# sc.net
KiCad netlist of a schematic drawn in EAGLE
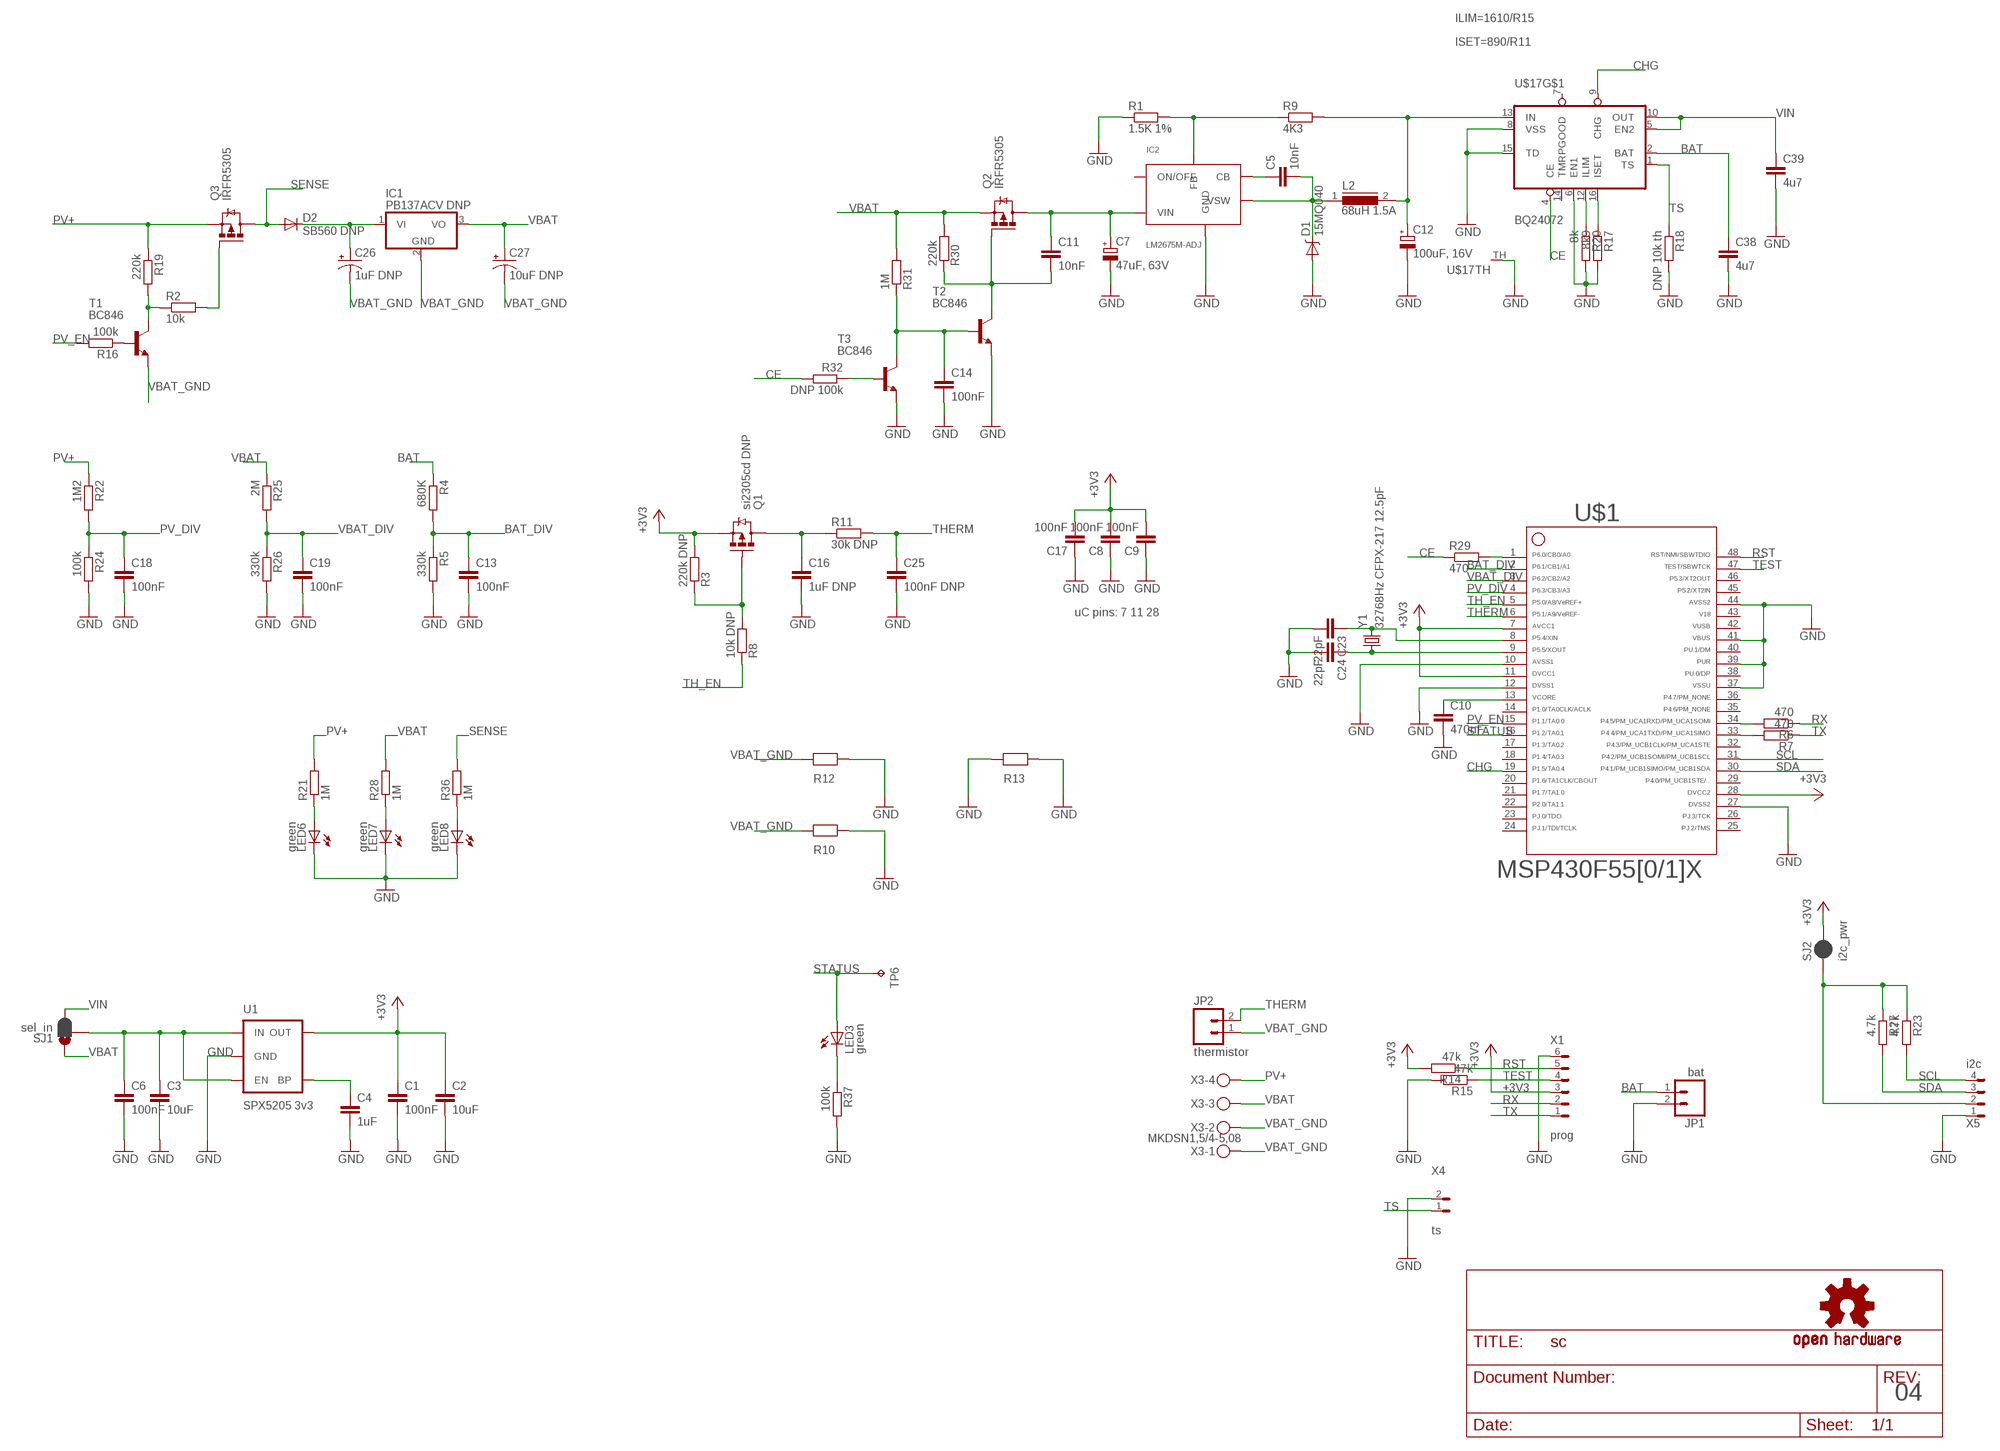
[diagram p0: schematic, sheet 1]

(export (version "E")
  (design (tool "Eeschema 10.0.6"))
  (components
    (comp (ref "C1")
      (value "100nF")
      (footprint "eagle-import:C0805")
      (libsource (lib "eagle-import") (part "C-EUC0805"))
    )
    (comp (ref "C2")
      (value "10uF")
      (footprint "eagle-import:C1206")
      (libsource (lib "eagle-import") (part "C-EUC1206"))
    )
    (comp (ref "C3")
      (value "10uF")
      (footprint "eagle-import:C1206")
      (libsource (lib "eagle-import") (part "C-EUC1206"))
    )
    (comp (ref "C4")
      (value "1uF")
      (footprint "eagle-import:C0805")
      (libsource (lib "eagle-import") (part "C-EUC0805"))
    )
    (comp (ref "C5")
      (value "10nF")
      (footprint "eagle-import:C0805")
      (libsource (lib "eagle-import") (part "C-EUC0805"))
    )
    (comp (ref "C6")
      (value "100nF")
      (footprint "eagle-import:C0805")
      (libsource (lib "eagle-import") (part "C-EUC0805"))
    )
    (comp (ref "C7")
      (value "47uF, 63V")
      (footprint "eagle-import:PANASONIC_F")
      (libsource (lib "eagle-import") (part "CPOL-EUF"))
    )
    (comp (ref "C8")
      (value "100nF")
      (footprint "eagle-import:C0805")
      (libsource (lib "eagle-import") (part "C-EUC0805"))
    )
    (comp (ref "C9")
      (value "100nF")
      (footprint "eagle-import:C0805")
      (libsource (lib "eagle-import") (part "C-EUC0805"))
    )
    (comp (ref "C10")
      (value "470nF")
      (footprint "eagle-import:C0805")
      (libsource (lib "eagle-import") (part "C-EUC0805"))
    )
    (comp (ref "C11")
      (value "10nF")
      (footprint "eagle-import:C0805")
      (libsource (lib "eagle-import") (part "C-EUC0805"))
    )
    (comp (ref "C12")
      (value "100uF, 16V")
      (footprint "eagle-import:PANASONIC_D")
      (libsource (lib "eagle-import") (part "CPOL-EUD"))
    )
    (comp (ref "C13")
      (value "100nF")
      (footprint "eagle-import:C0805")
      (libsource (lib "eagle-import") (part "C-EUC0805"))
    )
    (comp (ref "C14")
      (value "100nF")
      (footprint "eagle-import:C0805")
      (libsource (lib "eagle-import") (part "C-EUC0805"))
    )
    (comp (ref "C16")
      (value "1uF DNP")
      (footprint "eagle-import:C0805")
      (libsource (lib "eagle-import") (part "C-EUC0805"))
    )
    (comp (ref "C17")
      (value "100nF")
      (footprint "eagle-import:C0805")
      (libsource (lib "eagle-import") (part "C-EUC0805"))
    )
    (comp (ref "C18")
      (value "100nF")
      (footprint "eagle-import:C0805")
      (libsource (lib "eagle-import") (part "C-EUC0805"))
    )
    (comp (ref "C19")
      (value "100nF")
      (footprint "eagle-import:C0805")
      (libsource (lib "eagle-import") (part "C-EUC0805"))
    )
    (comp (ref "C23")
      (value "22pF")
      (footprint "eagle-import:C0805")
      (libsource (lib "eagle-import") (part "C-EUC0805"))
    )
    (comp (ref "C24")
      (value "22pF")
      (footprint "eagle-import:C0805")
      (libsource (lib "eagle-import") (part "C-EUC0805"))
    )
    (comp (ref "C25")
      (value "100nF DNP")
      (footprint "eagle-import:C0805")
      (libsource (lib "eagle-import") (part "C-EUC0805"))
    )
    (comp (ref "C26")
      (value "1uF DNP")
      (footprint "eagle-import:PANASONIC_D")
      (libsource (lib "eagle-import") (part "CAP_POLD"))
    )
    (comp (ref "C27")
      (value "10uF DNP")
      (footprint "eagle-import:PANASONIC_D")
      (libsource (lib "eagle-import") (part "CAP_POLD"))
    )
    (comp (ref "C38")
      (value "4u7")
      (footprint "eagle-import:C1206")
      (libsource (lib "eagle-import") (part "C-EUC1206"))
    )
    (comp (ref "C39")
      (value "4u7")
      (footprint "eagle-import:C1206")
      (libsource (lib "eagle-import") (part "C-EUC1206"))
    )
    (comp (ref "D1")
      (value "15MQ040")
      (footprint "eagle-import:SMA-DIODE")
      (libsource (lib "eagle-import") (part "DIODE-SCHOTTKY-MBRA140"))
    )
    (comp (ref "D2")
      (value "SB560 DNP")
      (footprint "eagle-import:C1702-05")
      (libsource (lib "eagle-import") (part "DIODE-C1702-05"))
    )
    (comp (ref "IC1")
      (value "PB137ACV DNP")
      (footprint "eagle-import:TO220V")
      (libsource (lib "eagle-import") (part "78TV12"))
    )
    (comp (ref "IC2")
      (value "LM2675M-ADJ")
      (footprint "eagle-import:SO-08")
      (libsource (lib "eagle-import") (part "LM2674"))
    )
    (comp (ref "JP1")
      (value "bat")
      (footprint "eagle-import:1X02")
      (libsource (lib "eagle-import") (part "M02PTH"))
    )
    (comp (ref "JP2")
      (value "thermistor")
      (footprint "eagle-import:1X02")
      (libsource (lib "eagle-import") (part "M02PTH"))
    )
    (comp (ref "L2")
      (value "68uH 1.5A")
      (footprint "eagle-import:DR125")
      (libsource (lib "eagle-import") (part "DR125"))
    )
    (comp (ref "LED3")
      (value "green")
      (footprint "eagle-import:CHIPLED_0805")
      (libsource (lib "eagle-import") (part "LEDCHIPLED_0805"))
    )
    (comp (ref "LED6")
      (value "green")
      (footprint "eagle-import:CHIP-LED0805")
      (libsource (lib "eagle-import") (part "LEDCHIP-LED0805"))
    )
    (comp (ref "LED7")
      (value "green")
      (footprint "eagle-import:CHIP-LED0805")
      (libsource (lib "eagle-import") (part "LEDCHIP-LED0805"))
    )
    (comp (ref "LED8")
      (value "green")
      (footprint "eagle-import:CHIP-LED0805")
      (libsource (lib "eagle-import") (part "LEDCHIP-LED0805"))
    )
    (comp (ref "Q1")
      (value "si2305cd DNP")
      (footprint "eagle-import:SOT23-3_POWER@1")
      (libsource (lib "eagle-import") (part "MOSFET-PCHANNELSMD_POWER"))
    )
    (comp (ref "Q2")
      (value "IRFR5305")
      (footprint "eagle-import:D-PAK_TO252AA")
      (libsource (lib "eagle-import") (part "IRF?5305R"))
    )
    (comp (ref "Q3")
      (value "IRFR5305")
      (footprint "eagle-import:D-PAK_TO252AA")
      (libsource (lib "eagle-import") (part "IRF?5305R"))
    )
    (comp (ref "R1")
      (value "1.5K 1%")
      (footprint "eagle-import:R0805W")
      (libsource (lib "eagle-import") (part "R-EU_R0805W"))
    )
    (comp (ref "R2")
      (value "10k")
      (footprint "eagle-import:R0805W")
      (libsource (lib "eagle-import") (part "R-EU_R0805W"))
    )
    (comp (ref "R3")
      (value "220k DNP")
      (footprint "eagle-import:R0805W")
      (libsource (lib "eagle-import") (part "R-EU_R0805W"))
    )
    (comp (ref "R4")
      (value "680K")
      (footprint "eagle-import:R0805W")
      (libsource (lib "eagle-import") (part "R-EU_R0805W"))
    )
    (comp (ref "R5")
      (value "330k")
      (footprint "eagle-import:R0805W")
      (libsource (lib "eagle-import") (part "R-EU_R0805W"))
    )
    (comp (ref "R6")
      (value "470")
      (footprint "eagle-import:R0805W")
      (libsource (lib "eagle-import") (part "R-EU_R0805W"))
    )
    (comp (ref "R7")
      (value "470")
      (footprint "eagle-import:R0805W")
      (libsource (lib "eagle-import") (part "R-EU_R0805W"))
    )
    (comp (ref "R8")
      (value "10k DNP")
      (footprint "eagle-import:R0805W")
      (libsource (lib "eagle-import") (part "R-EU_R0805W"))
    )
    (comp (ref "R9")
      (value "4K3")
      (footprint "eagle-import:R0805W")
      (libsource (lib "eagle-import") (part "R-EU_R0805W"))
    )
    (comp (ref "R10")
      (value "0R_0805")
      (footprint "eagle-import:R0805W")
      (libsource (lib "eagle-import") (part "0R_0805"))
    )
    (comp (ref "R11")
      (value "30k DNP")
      (footprint "eagle-import:R0805W")
      (libsource (lib "eagle-import") (part "R-EU_R0805W"))
    )
    (comp (ref "R12")
      (value "0R_0805")
      (footprint "eagle-import:R0805W")
      (libsource (lib "eagle-import") (part "0R_0805"))
    )
    (comp (ref "R13")
      (value "0R_0805")
      (footprint "eagle-import:R0805W")
      (libsource (lib "eagle-import") (part "0R_0805"))
    )
    (comp (ref "R14")
      (value "47k")
      (footprint "eagle-import:R0805W")
      (libsource (lib "eagle-import") (part "R-EU_R0805W"))
    )
    (comp (ref "R15")
      (value "47k")
      (footprint "eagle-import:R0805W")
      (libsource (lib "eagle-import") (part "R-EU_R0805W"))
    )
    (comp (ref "R16")
      (value "100k")
      (footprint "eagle-import:R0805W")
      (libsource (lib "eagle-import") (part "R-EU_R0805W"))
    )
    (comp (ref "R17")
      (value "8k9")
      (footprint "eagle-import:R0805W")
      (libsource (lib "eagle-import") (part "R-EU_R0805W"))
    )
    (comp (ref "R18")
      (value "DNP 10k th")
      (footprint "eagle-import:R0805W")
      (libsource (lib "eagle-import") (part "R-EU_R0805W"))
    )
    (comp (ref "R19")
      (value "220k")
      (footprint "eagle-import:R0805W")
      (libsource (lib "eagle-import") (part "R-EU_R0805W"))
    )
    (comp (ref "R20")
      (value "8k")
      (footprint "eagle-import:R0805W")
      (libsource (lib "eagle-import") (part "R-EU_R0805W"))
    )
    (comp (ref "R21")
      (value "1M")
      (footprint "eagle-import:R0805W")
      (libsource (lib "eagle-import") (part "R-EU_R0805W"))
    )
    (comp (ref "R22")
      (value "1M2")
      (footprint "eagle-import:R0805W")
      (libsource (lib "eagle-import") (part "R-EU_R0805W"))
    )
    (comp (ref "R23")
      (value "4.7k")
      (footprint "eagle-import:R0805W")
      (libsource (lib "eagle-import") (part "R-EU_R0805W"))
    )
    (comp (ref "R24")
      (value "100k")
      (footprint "eagle-import:R0805W")
      (libsource (lib "eagle-import") (part "R-EU_R0805W"))
    )
    (comp (ref "R25")
      (value "2M")
      (footprint "eagle-import:R0805W")
      (libsource (lib "eagle-import") (part "R-EU_R0805W"))
    )
    (comp (ref "R26")
      (value "330k")
      (footprint "eagle-import:R0805W")
      (libsource (lib "eagle-import") (part "R-EU_R0805W"))
    )
    (comp (ref "R27")
      (value "4.7k")
      (footprint "eagle-import:R0805W")
      (libsource (lib "eagle-import") (part "R-EU_R0805W"))
    )
    (comp (ref "R28")
      (value "1M")
      (footprint "eagle-import:R0805W")
      (libsource (lib "eagle-import") (part "R-EU_R0805W"))
    )
    (comp (ref "R29")
      (value "470")
      (footprint "eagle-import:R0805W")
      (libsource (lib "eagle-import") (part "R-EU_R0805W"))
    )
    (comp (ref "R30")
      (value "220k")
      (footprint "eagle-import:R0805W")
      (libsource (lib "eagle-import") (part "R-EU_R0805W"))
    )
    (comp (ref "R31")
      (value "1M")
      (footprint "eagle-import:R0805W")
      (libsource (lib "eagle-import") (part "R-EU_R0805W"))
    )
    (comp (ref "R32")
      (value "DNP 100k")
      (footprint "eagle-import:R0805W")
      (libsource (lib "eagle-import") (part "R-EU_R0805W"))
    )
    (comp (ref "R36")
      (value "1M")
      (footprint "eagle-import:R0805W")
      (libsource (lib "eagle-import") (part "R-EU_R0805W"))
    )
    (comp (ref "R37")
      (value "100k")
      (footprint "eagle-import:R0805W")
      (libsource (lib "eagle-import") (part "R-EU_R0805W"))
    )
    (comp (ref "SJ1")
      (value "sel_in")
      (footprint "eagle-import:PAD-JUMPER-3-2OF3_NC_BY_PASTE_YES_SILK_FULL_BOX")
      (libsource (lib "eagle-import") (part "JUMPER-PAD-3-2OF3_NC_BY_PASTE"))
    )
    (comp (ref "SJ2")
      (value "i2c_pwr")
      (footprint "eagle-import:PAD-JUMPER-2-NC_BY_PASTE_YES_SILK")
      (libsource (lib "eagle-import") (part "JUMPER-PAD-2-NC_BY_PASTE"))
    )
    (comp (ref "T1")
      (value "BC846")
      (footprint "eagle-import:SOT23")
      (libsource (lib "eagle-import") (part "BC846"))
    )
    (comp (ref "T2")
      (value "BC846")
      (footprint "eagle-import:SOT23")
      (libsource (lib "eagle-import") (part "BC846"))
    )
    (comp (ref "T3")
      (value "BC846")
      (footprint "eagle-import:SOT23")
      (libsource (lib "eagle-import") (part "BC846"))
    )
    (comp (ref "TP6")
      (value "TPTP12R")
      (footprint "eagle-import:TP12R")
      (libsource (lib "eagle-import") (part "TPTP12R"))
    )
    (comp (ref "U$1")
      (value "F55[0/1]X---PT48")
      (footprint "eagle-import:PT48")
      (libsource (lib "eagle-import") (part "F55[0/1]X---PT48"))
    )
    (comp (ref "U$7")
      (value "OSHW-LOGOM")
      (footprint "eagle-import:OSHW-LOGO-M")
      (libsource (lib "eagle-import") (part "OSHW-LOGOM"))
    )
    (comp (ref "U$17")
      (value "BQ24072")
      (footprint "eagle-import:S-PVQFN-N16")
      (libsource (lib "eagle-import") (part "BQ24072"))
    )
    (comp (ref "U1")
      (value "SPX5205 3v3")
      (footprint "eagle-import:SOT23-5")
      (libsource (lib "eagle-import") (part "V_REG_LDOSMD"))
    )
    (comp (ref "X1")
      (value "prog")
      (footprint "eagle-import:0530480610")
      (libsource (lib "eagle-import") (part "MOLEX_6HORIZONTAL"))
    )
    (comp (ref "X3")
      (value "MKDSN1,5/4-5,08")
      (footprint "eagle-import:MKDSN1,5_4-5,08")
      (fields (field (name "MPN") "SMKDSN1,5/4-5,08"))
      (libsource (lib "eagle-import") (part "MKDSN1,5/4-5,08"))
    )
    (comp (ref "X4")
      (value "ts")
      (footprint "eagle-import:0530480210")
      (libsource (lib "eagle-import") (part "MOLEX_2HORIZONTAL"))
    )
    (comp (ref "X5")
      (value "i2c")
      (footprint "eagle-import:0530480401")
      (libsource (lib "eagle-import") (part "MOLEX_4HORIZONTAL"))
    )
    (comp (ref "Y1")
      (value "32768Hz CFPX-217 12.5pF")
      (footprint "eagle-import:CRYSTAL-SMD-3.2X1.5")
      (libsource (lib "eagle-import") (part "CRYSTAL3.2X1.5"))
    )
  )
  (nets
    (net (code "1") (name "+3V3") (class "Default")
      (node (ref "C1") (pin "1") (pinfunction "1_1") (pintype "passive"))
      (node (ref "C17") (pin "2") (pinfunction "2_2") (pintype "passive"))
      (node (ref "C2") (pin "1") (pinfunction "1_1") (pintype "passive"))
      (node (ref "C8") (pin "2") (pinfunction "2_2") (pintype "passive"))
      (node (ref "C9") (pin "2") (pinfunction "2_2") (pintype "passive"))
      (node (ref "Q1") (pin "2") (pinfunction "S_2") (pintype "passive"))
      (node (ref "R14") (pin "2") (pinfunction "2_2") (pintype "passive"))
      (node (ref "R3") (pin "2") (pinfunction "2_2") (pintype "passive"))
      (node (ref "SJ2") (pin "2") (pinfunction "2_2") (pintype "passive"))
      (node (ref "U$1") (pin "11") (pinfunction "11_11") (pintype "power_in"))
      (node (ref "U$1") (pin "28") (pinfunction "28_28") (pintype "power_in"))
      (node (ref "U$1") (pin "7") (pinfunction "7_7") (pintype "power_in"))
      (node (ref "U1") (pin "5") (pinfunction "OUT_5") (pintype "passive"))
      (node (ref "X1") (pin "3") (pinfunction "4_3") (pintype "passive"))
    )
    (net (code "2") (name "/42") (class "Default")
      (node (ref "U$1") (pin "42") (pinfunction "42_42") (pintype "power_in"))
    )
    (net (code "3") (name "/43") (class "Default")
      (node (ref "U$1") (pin "43") (pinfunction "43_43") (pintype "power_in"))
    )
    (net (code "4") (name "/46") (class "Default")
      (node (ref "U$1") (pin "46") (pinfunction "46_46") (pintype "power_in"))
    )
    (net (code "5") (name "/BAT") (class "Default")
      (node (ref "C38") (pin "1") (pinfunction "1_1") (pintype "passive"))
      (node (ref "JP1") (pin "1") (pinfunction "1_1") (pintype "passive"))
      (node (ref "R4") (pin "1") (pinfunction "1_1") (pintype "passive"))
      (node (ref "U$17") (pin "2") (pinfunction "BAT_2") (pintype "input"))
    )
    (net (code "6") (name "/BAT_DIV") (class "Default")
      (node (ref "C13") (pin "1") (pinfunction "1_1") (pintype "passive"))
      (node (ref "R4") (pin "2") (pinfunction "2_2") (pintype "passive"))
      (node (ref "R5") (pin "1") (pinfunction "1_1") (pintype "passive"))
      (node (ref "U$1") (pin "2") (pinfunction "2_2") (pintype "bidirectional"))
    )
    (net (code "7") (name "/CE") (class "Default")
      (node (ref "R29") (pin "1") (pinfunction "1_1") (pintype "passive"))
      (node (ref "R32") (pin "2") (pinfunction "2_2") (pintype "passive"))
      (node (ref "U$17") (pin "4") (pinfunction "CE_4") (pintype "bidirectional"))
    )
    (net (code "8") (name "/CHG") (class "Default")
      (node (ref "U$1") (pin "19") (pinfunction "19_19") (pintype "bidirectional"))
      (node (ref "U$17") (pin "9") (pinfunction "CHG_9") (pintype "bidirectional"))
    )
    (net (code "9") (name "/PV+") (class "Default")
      (node (ref "Q3") (pin "3") (pinfunction "S_3") (pintype "passive"))
      (node (ref "R19") (pin "1") (pinfunction "1_1") (pintype "passive"))
      (node (ref "R21") (pin "2") (pinfunction "2_2") (pintype "passive"))
      (node (ref "R22") (pin "1") (pinfunction "1_1") (pintype "passive"))
      (node (ref "X3") (pin "4") (pinfunction "KL_4") (pintype "passive"))
    )
    (net (code "10") (name "/PV_DIV") (class "Default")
      (node (ref "C18") (pin "1") (pinfunction "1_1") (pintype "passive"))
      (node (ref "R22") (pin "2") (pinfunction "2_2") (pintype "passive"))
      (node (ref "R24") (pin "1") (pinfunction "1_1") (pintype "passive"))
      (node (ref "U$1") (pin "4") (pinfunction "4_4") (pintype "bidirectional"))
    )
    (net (code "11") (name "/PV_EN") (class "Default")
      (node (ref "R16") (pin "2") (pinfunction "2_2") (pintype "passive"))
      (node (ref "U$1") (pin "15") (pinfunction "15_15") (pintype "bidirectional"))
    )
    (net (code "12") (name "/RST") (class "Default")
      (node (ref "R14") (pin "1") (pinfunction "1_1") (pintype "passive"))
      (node (ref "U$1") (pin "48") (pinfunction "48_48") (pintype "bidirectional"))
      (node (ref "X1") (pin "5") (pinfunction "2_5") (pintype "passive"))
    )
    (net (code "13") (name "/RX") (class "Default")
      (node (ref "R6") (pin "1") (pinfunction "1_1") (pintype "passive"))
      (node (ref "X1") (pin "2") (pinfunction "5_2") (pintype "passive"))
    )
    (net (code "14") (name "/SCL") (class "Default")
      (node (ref "R23") (pin "2") (pinfunction "2_2") (pintype "passive"))
      (node (ref "U$1") (pin "31") (pinfunction "31_31") (pintype "bidirectional"))
      (node (ref "X5") (pin "4") (pinfunction "1_4") (pintype "passive"))
    )
    (net (code "15") (name "/SDA") (class "Default")
      (node (ref "R27") (pin "2") (pinfunction "2_2") (pintype "passive"))
      (node (ref "U$1") (pin "30") (pinfunction "30_30") (pintype "bidirectional"))
      (node (ref "X5") (pin "3") (pinfunction "2_3") (pintype "passive"))
    )
    (net (code "16") (name "/SENSE") (class "Default")
      (node (ref "D2") (pin "A") (pinfunction "A_A") (pintype "passive"))
      (node (ref "Q3") (pin "4") (pinfunction "D_4") (pintype "passive"))
      (node (ref "R36") (pin "2") (pinfunction "2_2") (pintype "passive"))
    )
    (net (code "17") (name "/STATUS") (class "Default")
      (node (ref "LED3") (pin "A") (pinfunction "A_A") (pintype "passive"))
      (node (ref "TP6") (pin "TP") (pinfunction "TP_TP") (pintype "input"))
      (node (ref "U$1") (pin "16") (pinfunction "16_16") (pintype "bidirectional"))
    )
    (net (code "18") (name "/TEST") (class "Default")
      (node (ref "R15") (pin "1") (pinfunction "1_1") (pintype "passive"))
      (node (ref "U$1") (pin "47") (pinfunction "47_47") (pintype "input"))
      (node (ref "X1") (pin "4") (pinfunction "3_4") (pintype "passive"))
    )
    (net (code "19") (name "/THERM") (class "Default")
      (node (ref "C25") (pin "1") (pinfunction "1_1") (pintype "passive"))
      (node (ref "JP2") (pin "2") (pinfunction "2_2") (pintype "passive"))
      (node (ref "R11") (pin "2") (pinfunction "2_2") (pintype "passive"))
      (node (ref "U$1") (pin "6") (pinfunction "6_6") (pintype "bidirectional"))
    )
    (net (code "20") (name "/TH_EN") (class "Default")
      (node (ref "R8") (pin "1") (pinfunction "1_1") (pintype "passive"))
      (node (ref "U$1") (pin "5") (pinfunction "5_5") (pintype "bidirectional"))
    )
    (net (code "21") (name "/TS") (class "Default")
      (node (ref "R18") (pin "1") (pinfunction "1_1") (pintype "passive"))
      (node (ref "U$17") (pin "1") (pinfunction "TS_1") (pintype "input"))
      (node (ref "X4") (pin "1") (pinfunction "2_1") (pintype "passive"))
    )
    (net (code "22") (name "/TX") (class "Default")
      (node (ref "R7") (pin "1") (pinfunction "1_1") (pintype "passive"))
      (node (ref "X1") (pin "1") (pinfunction "6_1") (pintype "passive"))
    )
    (net (code "23") (name "/VBAT") (class "Default")
      (node (ref "C27") (pin "+") (pinfunction "+_+") (pintype "passive"))
      (node (ref "IC1") (pin "3") (pinfunction "VO_3") (pintype "passive"))
      (node (ref "Q2") (pin "3") (pinfunction "S_3") (pintype "passive"))
      (node (ref "R25") (pin "1") (pinfunction "1_1") (pintype "passive"))
      (node (ref "R28") (pin "2") (pinfunction "2_2") (pintype "passive"))
      (node (ref "R30") (pin "2") (pinfunction "2_2") (pintype "passive"))
      (node (ref "R31") (pin "2") (pinfunction "2_2") (pintype "passive"))
      (node (ref "SJ1") (pin "1") (pinfunction "1_1") (pintype "passive"))
      (node (ref "X3") (pin "3") (pinfunction "KL_3") (pintype "passive"))
    )
    (net (code "24") (name "/VBAT_DIV") (class "Default")
      (node (ref "C19") (pin "1") (pinfunction "1_1") (pintype "passive"))
      (node (ref "R25") (pin "2") (pinfunction "2_2") (pintype "passive"))
      (node (ref "R26") (pin "1") (pinfunction "1_1") (pintype "passive"))
      (node (ref "U$1") (pin "3") (pinfunction "3_3") (pintype "bidirectional"))
    )
    (net (code "25") (name "/VBAT_GND") (class "Default")
      (node (ref "C26") (pin "-") (pinfunction "-_-") (pintype "passive"))
      (node (ref "C27") (pin "-") (pinfunction "-_-") (pintype "passive"))
      (node (ref "IC1") (pin "2") (pinfunction "GND_2") (pintype "passive"))
      (node (ref "JP2") (pin "1") (pinfunction "1_1") (pintype "passive"))
      (node (ref "R10") (pin "1") (pinfunction "P$1_1") (pintype "bidirectional"))
      (node (ref "R12") (pin "1") (pinfunction "P$1_1") (pintype "bidirectional"))
      (node (ref "T1") (pin "2") (pinfunction "E_2") (pintype "passive"))
      (node (ref "X3") (pin "1") (pinfunction "KL_1") (pintype "passive"))
      (node (ref "X3") (pin "2") (pinfunction "KL_2") (pintype "passive"))
    )
    (net (code "26") (name "/VIN") (class "Default")
      (node (ref "C39") (pin "1") (pinfunction "1_1") (pintype "passive"))
      (node (ref "SJ1") (pin "3") (pinfunction "3_3") (pintype "passive"))
      (node (ref "U$17") (pin "10") (pinfunction "OUT_10") (pintype "output"))
      (node (ref "U$17") (pin "5") (pinfunction "EN2_5") (pintype "input"))
    )
    (net (code "27") (name "GND") (class "Default")
      (node (ref "C1") (pin "2") (pinfunction "2_2") (pintype "passive"))
      (node (ref "C10") (pin "2") (pinfunction "2_2") (pintype "passive"))
      (node (ref "C12") (pin "-") (pinfunction "-_-") (pintype "passive"))
      (node (ref "C13") (pin "2") (pinfunction "2_2") (pintype "passive"))
      (node (ref "C14") (pin "2") (pinfunction "2_2") (pintype "passive"))
      (node (ref "C16") (pin "2") (pinfunction "2_2") (pintype "passive"))
      (node (ref "C17") (pin "1") (pinfunction "1_1") (pintype "passive"))
      (node (ref "C18") (pin "2") (pinfunction "2_2") (pintype "passive"))
      (node (ref "C19") (pin "2") (pinfunction "2_2") (pintype "passive"))
      (node (ref "C2") (pin "2") (pinfunction "2_2") (pintype "passive"))
      (node (ref "C23") (pin "2") (pinfunction "2_2") (pintype "passive"))
      (node (ref "C24") (pin "2") (pinfunction "2_2") (pintype "passive"))
      (node (ref "C25") (pin "2") (pinfunction "2_2") (pintype "passive"))
      (node (ref "C3") (pin "2") (pinfunction "2_2") (pintype "passive"))
      (node (ref "C38") (pin "2") (pinfunction "2_2") (pintype "passive"))
      (node (ref "C39") (pin "2") (pinfunction "2_2") (pintype "passive"))
      (node (ref "C4") (pin "2") (pinfunction "2_2") (pintype "passive"))
      (node (ref "C6") (pin "2") (pinfunction "2_2") (pintype "passive"))
      (node (ref "C7") (pin "-") (pinfunction "-_-") (pintype "passive"))
      (node (ref "C8") (pin "1") (pinfunction "1_1") (pintype "passive"))
      (node (ref "C9") (pin "1") (pinfunction "1_1") (pintype "passive"))
      (node (ref "D1") (pin "A") (pinfunction "A_A") (pintype "passive"))
      (node (ref "IC2") (pin "6") (pinfunction "GND_6") (pintype "bidirectional"))
      (node (ref "JP1") (pin "2") (pinfunction "2_2") (pintype "passive"))
      (node (ref "LED6") (pin "C") (pinfunction "C_C") (pintype "passive"))
      (node (ref "LED7") (pin "C") (pinfunction "C_C") (pintype "passive"))
      (node (ref "LED8") (pin "C") (pinfunction "C_C") (pintype "passive"))
      (node (ref "R1") (pin "1") (pinfunction "1_1") (pintype "passive"))
      (node (ref "R10") (pin "2") (pinfunction "P$2_2") (pintype "bidirectional"))
      (node (ref "R12") (pin "2") (pinfunction "P$2_2") (pintype "bidirectional"))
      (node (ref "R13") (pin "1") (pinfunction "P$1_1") (pintype "bidirectional"))
      (node (ref "R13") (pin "2") (pinfunction "P$2_2") (pintype "bidirectional"))
      (node (ref "R15") (pin "2") (pinfunction "2_2") (pintype "passive"))
      (node (ref "R17") (pin "2") (pinfunction "2_2") (pintype "passive"))
      (node (ref "R18") (pin "2") (pinfunction "2_2") (pintype "passive"))
      (node (ref "R20") (pin "2") (pinfunction "2_2") (pintype "passive"))
      (node (ref "R24") (pin "2") (pinfunction "2_2") (pintype "passive"))
      (node (ref "R26") (pin "2") (pinfunction "2_2") (pintype "passive"))
      (node (ref "R37") (pin "2") (pinfunction "2_2") (pintype "passive"))
      (node (ref "R5") (pin "2") (pinfunction "2_2") (pintype "passive"))
      (node (ref "T2") (pin "2") (pinfunction "E_2") (pintype "passive"))
      (node (ref "T3") (pin "2") (pinfunction "E_2") (pintype "passive"))
      (node (ref "U$1") (pin "10") (pinfunction "10_10") (pintype "power_in"))
      (node (ref "U$1") (pin "12") (pinfunction "12_12") (pintype "power_in"))
      (node (ref "U$1") (pin "27") (pinfunction "27_27") (pintype "power_in"))
      (node (ref "U$1") (pin "37") (pinfunction "37_37") (pintype "power_in"))
      (node (ref "U$1") (pin "39") (pinfunction "39_39") (pintype "bidirectional"))
      (node (ref "U$1") (pin "41") (pinfunction "41_41") (pintype "power_in"))
      (node (ref "U$1") (pin "44") (pinfunction "44_44") (pintype "power_in"))
      (node (ref "U$17") (pin "15") (pinfunction "TD_15") (pintype "bidirectional"))
      (node (ref "U$17") (pin "6") (pinfunction "EN1_6") (pintype "bidirectional"))
      (node (ref "U$17") (pin "8") (pinfunction "VSS_8") (pintype "power_in"))
      (node (ref "U$17") (pin "TH") (pinfunction "TH_TH") (pintype "passive"))
      (node (ref "U1") (pin "2") (pinfunction "GND_2") (pintype "input"))
      (node (ref "X1") (pin "6") (pinfunction "1_6") (pintype "passive"))
      (node (ref "X4") (pin "2") (pinfunction "1_2") (pintype "passive"))
      (node (ref "X5") (pin "1") (pinfunction "4_1") (pintype "passive"))
    )
    (net (code "28") (name "Net-(C10-Pad1)") (class "Default")
      (node (ref "C10") (pin "1") (pinfunction "1_1") (pintype "passive"))
      (node (ref "U$1") (pin "13") (pinfunction "13_13") (pintype "power_in"))
    )
    (net (code "29") (name "Net-(IC1-VI)") (class "Default")
      (node (ref "C26") (pin "+") (pinfunction "+_+") (pintype "passive"))
      (node (ref "D2") (pin "C") (pinfunction "C_C") (pintype "passive"))
      (node (ref "IC1") (pin "1") (pinfunction "VI_1") (pintype "input"))
    )
    (net (code "30") (name "Net-(IC2-CB)") (class "Default")
      (node (ref "C5") (pin "1") (pinfunction "1_1") (pintype "passive"))
      (node (ref "IC2") (pin "1") (pinfunction "CB_1") (pintype "bidirectional"))
    )
    (net (code "31") (name "Net-(IC2-FB)") (class "Default")
      (node (ref "IC2") (pin "4") (pinfunction "FB_4") (pintype "bidirectional"))
      (node (ref "R1") (pin "2") (pinfunction "2_2") (pintype "passive"))
      (node (ref "R9") (pin "1") (pinfunction "1_1") (pintype "passive"))
    )
    (net (code "32") (name "Net-(IC2-VIN)") (class "Default")
      (node (ref "C11") (pin "1") (pinfunction "1_1") (pintype "passive"))
      (node (ref "C7") (pin "+") (pinfunction "+_+") (pintype "passive"))
      (node (ref "IC2") (pin "7") (pinfunction "VIN_7") (pintype "bidirectional"))
      (node (ref "Q2") (pin "4") (pinfunction "D_4") (pintype "passive"))
    )
    (net (code "33") (name "Net-(IC2-VSW)") (class "Default")
      (node (ref "C5") (pin "2") (pinfunction "2_2") (pintype "passive"))
      (node (ref "D1") (pin "C") (pinfunction "C_C") (pintype "passive"))
      (node (ref "IC2") (pin "8") (pinfunction "VSW_8") (pintype "bidirectional"))
      (node (ref "L2") (pin "1") (pinfunction "1_1") (pintype "passive"))
    )
    (net (code "34") (name "Net-(LED3-PadC)") (class "Default")
      (node (ref "LED3") (pin "C") (pinfunction "C_C") (pintype "passive"))
      (node (ref "R37") (pin "1") (pinfunction "1_1") (pintype "passive"))
    )
    (net (code "35") (name "Net-(LED6-PadA)") (class "Default")
      (node (ref "LED6") (pin "A") (pinfunction "A_A") (pintype "passive"))
      (node (ref "R21") (pin "1") (pinfunction "1_1") (pintype "passive"))
    )
    (net (code "36") (name "Net-(LED7-PadA)") (class "Default")
      (node (ref "LED7") (pin "A") (pinfunction "A_A") (pintype "passive"))
      (node (ref "R28") (pin "1") (pinfunction "1_1") (pintype "passive"))
    )
    (net (code "37") (name "Net-(LED8-PadA)") (class "Default")
      (node (ref "LED8") (pin "A") (pinfunction "A_A") (pintype "passive"))
      (node (ref "R36") (pin "1") (pinfunction "1_1") (pintype "passive"))
    )
    (net (code "38") (name "Net-(Q1-D)") (class "Default")
      (node (ref "C16") (pin "1") (pinfunction "1_1") (pintype "passive"))
      (node (ref "Q1") (pin "3") (pinfunction "D_3") (pintype "passive"))
      (node (ref "R11") (pin "1") (pinfunction "1_1") (pintype "passive"))
    )
    (net (code "39") (name "Net-(Q1-G)") (class "Default")
      (node (ref "Q1") (pin "1") (pinfunction "G_1") (pintype "passive"))
      (node (ref "R3") (pin "1") (pinfunction "1_1") (pintype "passive"))
      (node (ref "R8") (pin "2") (pinfunction "2_2") (pintype "passive"))
    )
    (net (code "40") (name "Net-(Q2-G)") (class "Default")
      (node (ref "C11") (pin "2") (pinfunction "2_2") (pintype "passive"))
      (node (ref "Q2") (pin "1") (pinfunction "G_1") (pintype "passive"))
      (node (ref "R30") (pin "1") (pinfunction "1_1") (pintype "passive"))
      (node (ref "T2") (pin "3") (pinfunction "C_3") (pintype "passive"))
    )
    (net (code "41") (name "Net-(Q3-G)") (class "Default")
      (node (ref "Q3") (pin "1") (pinfunction "G_1") (pintype "passive"))
      (node (ref "R2") (pin "2") (pinfunction "2_2") (pintype "passive"))
    )
    (net (code "42") (name "Net-(R6-Pad2)") (class "Default")
      (node (ref "R6") (pin "2") (pinfunction "2_2") (pintype "passive"))
      (node (ref "U$1") (pin "34") (pinfunction "34_34") (pintype "bidirectional"))
    )
    (net (code "43") (name "Net-(R7-Pad2)") (class "Default")
      (node (ref "R7") (pin "2") (pinfunction "2_2") (pintype "passive"))
      (node (ref "U$1") (pin "33") (pinfunction "33_33") (pintype "bidirectional"))
    )
    (net (code "44") (name "Net-(R29-Pad2)") (class "Default")
      (node (ref "R29") (pin "2") (pinfunction "2_2") (pintype "passive"))
      (node (ref "U$1") (pin "1") (pinfunction "1_1") (pintype "bidirectional"))
    )
    (net (code "45") (name "Net-(T1-B)") (class "Default")
      (node (ref "R16") (pin "1") (pinfunction "1_1") (pintype "passive"))
      (node (ref "T1") (pin "1") (pinfunction "B_1") (pintype "passive"))
    )
    (net (code "46") (name "Net-(T1-C)") (class "Default")
      (node (ref "R19") (pin "2") (pinfunction "2_2") (pintype "passive"))
      (node (ref "R2") (pin "1") (pinfunction "1_1") (pintype "passive"))
      (node (ref "T1") (pin "3") (pinfunction "C_3") (pintype "passive"))
    )
    (net (code "47") (name "Net-(T2-B)") (class "Default")
      (node (ref "C14") (pin "1") (pinfunction "1_1") (pintype "passive"))
      (node (ref "R31") (pin "1") (pinfunction "1_1") (pintype "passive"))
      (node (ref "T2") (pin "1") (pinfunction "B_1") (pintype "passive"))
      (node (ref "T3") (pin "3") (pinfunction "C_3") (pintype "passive"))
    )
    (net (code "48") (name "Net-(T3-B)") (class "Default")
      (node (ref "R32") (pin "1") (pinfunction "1_1") (pintype "passive"))
      (node (ref "T3") (pin "1") (pinfunction "B_1") (pintype "passive"))
    )
    (net (code "49") (name "Net-(U$17A-ILIM)") (class "Default")
      (node (ref "R20") (pin "1") (pinfunction "1_1") (pintype "passive"))
      (node (ref "U$17") (pin "12") (pinfunction "ILIM_12") (pintype "bidirectional"))
    )
    (net (code "50") (name "Net-(U$17A-IN)") (class "Default")
      (node (ref "C12") (pin "+") (pinfunction "+_+") (pintype "passive"))
      (node (ref "L2") (pin "2") (pinfunction "2_2") (pintype "passive"))
      (node (ref "R9") (pin "2") (pinfunction "2_2") (pintype "passive"))
      (node (ref "U$17") (pin "13") (pinfunction "IN_13") (pintype "input"))
    )
    (net (code "51") (name "Net-(U$17A-ISET)") (class "Default")
      (node (ref "R17") (pin "1") (pinfunction "1_1") (pintype "passive"))
      (node (ref "U$17") (pin "16") (pinfunction "ISET_16") (pintype "input"))
    )
    (net (code "52") (name "Net-(U1-BP)") (class "Default")
      (node (ref "C4") (pin "1") (pinfunction "1_1") (pintype "passive"))
      (node (ref "U1") (pin "4") (pinfunction "BP_4") (pintype "input"))
    )
    (net (code "53") (name "Net-(U1-EN)") (class "Default")
      (node (ref "C3") (pin "1") (pinfunction "1_1") (pintype "passive"))
      (node (ref "C6") (pin "1") (pinfunction "1_1") (pintype "passive"))
      (node (ref "SJ1") (pin "2") (pinfunction "2_2") (pintype "passive"))
      (node (ref "U1") (pin "1") (pinfunction "IN_1") (pintype "input"))
      (node (ref "U1") (pin "3") (pinfunction "EN_3") (pintype "input"))
    )
    (net (code "54") (name "Net-(X5-3)") (class "Default")
      (node (ref "R23") (pin "1") (pinfunction "1_1") (pintype "passive"))
      (node (ref "R27") (pin "1") (pinfunction "1_1") (pintype "passive"))
      (node (ref "SJ2") (pin "1") (pinfunction "1_1") (pintype "passive"))
      (node (ref "X5") (pin "2") (pinfunction "3_2") (pintype "passive"))
    )
    (net (code "55") (name "Net-(Y1-1)") (class "Default")
      (node (ref "C24") (pin "1") (pinfunction "1_1") (pintype "passive"))
      (node (ref "U$1") (pin "9") (pinfunction "9_9") (pintype "bidirectional"))
      (node (ref "Y1") (pin "P$1") (pinfunction "1_P$1") (pintype "passive"))
    )
    (net (code "56") (name "Net-(Y1-2)") (class "Default")
      (node (ref "C23") (pin "1") (pinfunction "1_1") (pintype "passive"))
      (node (ref "U$1") (pin "8") (pinfunction "8_8") (pintype "bidirectional"))
      (node (ref "Y1") (pin "P$2") (pinfunction "2_P$2") (pintype "passive"))
    )
    (net (code "57") (name "unconnected-(IC2-ON{slash}OFF-Pad5)") (class "Default")
      (node (ref "IC2") (pin "5") (pinfunction "ON/OFF_5") (pintype "bidirectional"))
    )
    (net (code "58") (name "unconnected-(U$1-Pad14)") (class "Default")
      (node (ref "U$1") (pin "14") (pinfunction "14_14") (pintype "bidirectional"))
    )
    (net (code "59") (name "unconnected-(U$1-Pad17)") (class "Default")
      (node (ref "U$1") (pin "17") (pinfunction "17_17") (pintype "bidirectional"))
    )
    (net (code "60") (name "unconnected-(U$1-Pad18)") (class "Default")
      (node (ref "U$1") (pin "18") (pinfunction "18_18") (pintype "bidirectional"))
    )
    (net (code "61") (name "unconnected-(U$1-Pad20)") (class "Default")
      (node (ref "U$1") (pin "20") (pinfunction "20_20") (pintype "bidirectional"))
    )
    (net (code "62") (name "unconnected-(U$1-Pad21)") (class "Default")
      (node (ref "U$1") (pin "21") (pinfunction "21_21") (pintype "bidirectional"))
    )
    (net (code "63") (name "unconnected-(U$1-Pad22)") (class "Default")
      (node (ref "U$1") (pin "22") (pinfunction "22_22") (pintype "bidirectional"))
    )
    (net (code "64") (name "unconnected-(U$1-Pad23)") (class "Default")
      (node (ref "U$1") (pin "23") (pinfunction "23_23") (pintype "bidirectional"))
    )
    (net (code "65") (name "unconnected-(U$1-Pad24)") (class "Default")
      (node (ref "U$1") (pin "24") (pinfunction "24_24") (pintype "bidirectional"))
    )
    (net (code "66") (name "unconnected-(U$1-Pad25)") (class "Default")
      (node (ref "U$1") (pin "25") (pinfunction "25_25") (pintype "bidirectional"))
    )
    (net (code "67") (name "unconnected-(U$1-Pad26)") (class "Default")
      (node (ref "U$1") (pin "26") (pinfunction "26_26") (pintype "bidirectional"))
    )
    (net (code "68") (name "unconnected-(U$1-Pad29)") (class "Default")
      (node (ref "U$1") (pin "29") (pinfunction "29_29") (pintype "bidirectional"))
    )
    (net (code "69") (name "unconnected-(U$1-Pad32)") (class "Default")
      (node (ref "U$1") (pin "32") (pinfunction "32_32") (pintype "bidirectional"))
    )
    (net (code "70") (name "unconnected-(U$1-Pad35)") (class "Default")
      (node (ref "U$1") (pin "35") (pinfunction "35_35") (pintype "bidirectional"))
    )
    (net (code "71") (name "unconnected-(U$1-Pad36)") (class "Default")
      (node (ref "U$1") (pin "36") (pinfunction "36_36") (pintype "bidirectional"))
    )
    (net (code "72") (name "unconnected-(U$1-Pad38)") (class "Default")
      (node (ref "U$1") (pin "38") (pinfunction "38_38") (pintype "bidirectional"))
    )
    (net (code "73") (name "unconnected-(U$1-Pad40)") (class "Default")
      (node (ref "U$1") (pin "40") (pinfunction "40_40") (pintype "bidirectional"))
    )
    (net (code "74") (name "unconnected-(U$1-Pad45)") (class "Default")
      (node (ref "U$1") (pin "45") (pinfunction "45_45") (pintype "bidirectional"))
    )
    (net (code "75") (name "unconnected-(U$17A-PGOOD-Pad7)") (class "Default")
      (node (ref "U$17") (pin "7") (pinfunction "PGOOD_7") (pintype "bidirectional"))
    )
    (net (code "76") (name "unconnected-(U$17A-TMR-Pad14)") (class "Default")
      (node (ref "U$17") (pin "14") (pinfunction "TMR_14") (pintype "bidirectional"))
    )
  )
)
